# Converter.net
KiCad netlist of a schematic drawn in Altium Designer
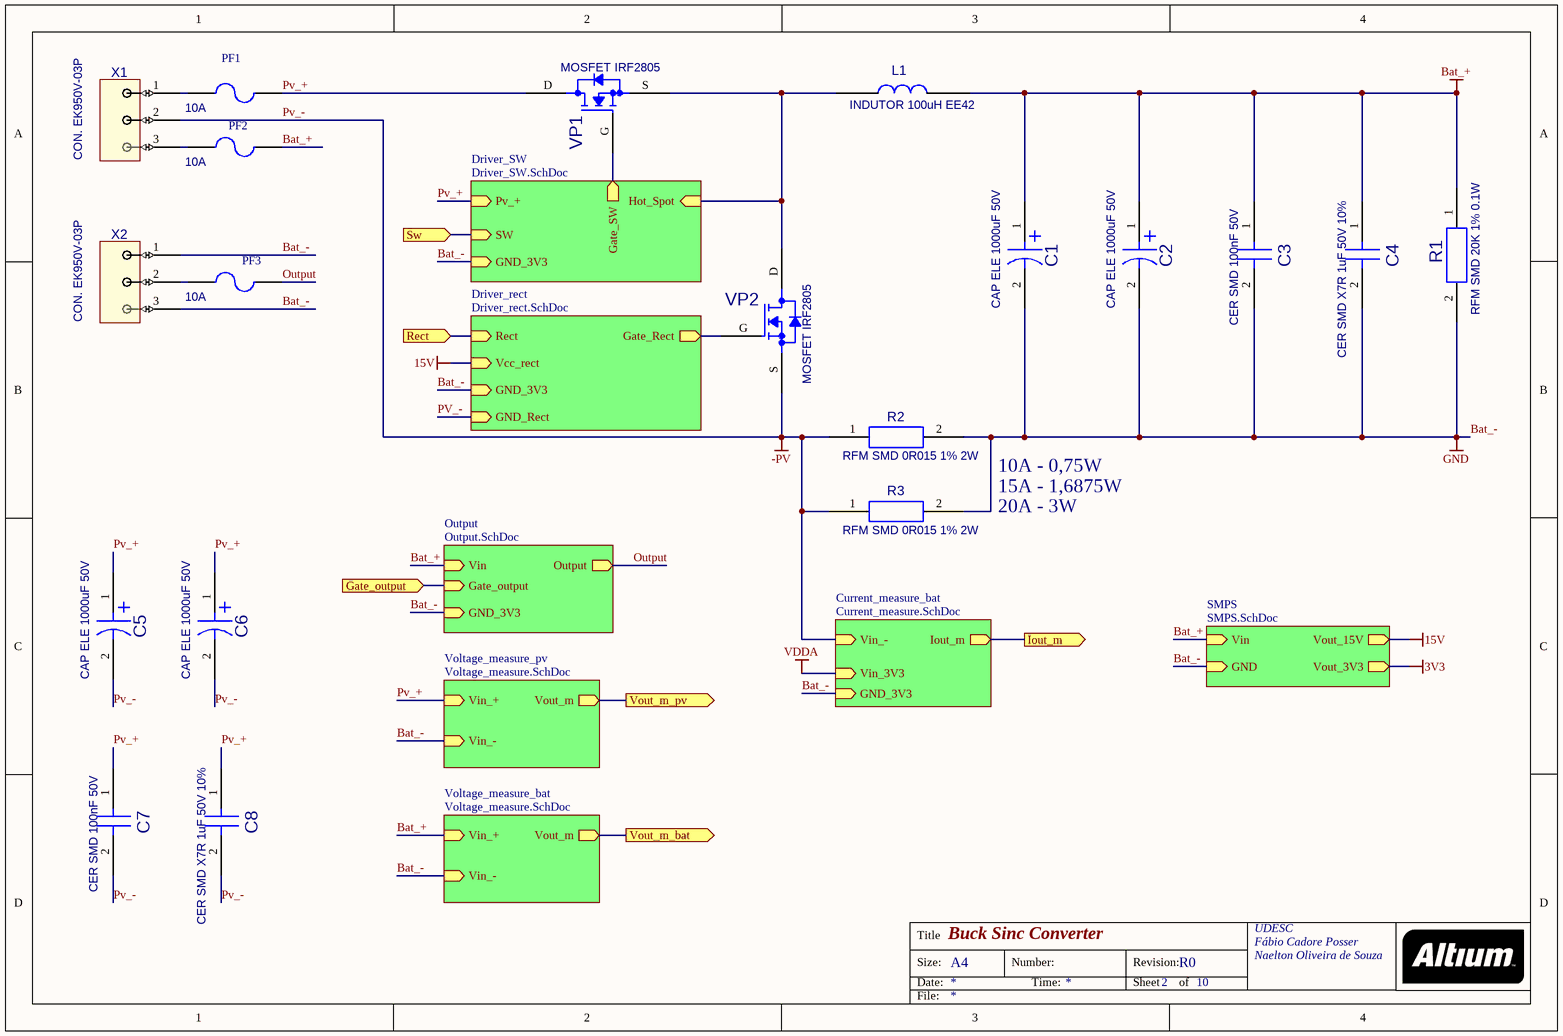
[diagram p0: Converter.SchDoc]

(export (version "E")
  (design (tool "Eeschema 10.0.6"))
  (components
    (comp (ref "C1")
      (value "CAP ELE 1000uF 50V")
      (footprint "CR 1.1 7.62 16.5")
      (fields (field (name "Comment") "10190340"))
      (libsource (lib "Buck_Converter") (part "10190340"))
    )
    (comp (ref "C2")
      (value "CAP ELE 1000uF 50V")
      (footprint "CR 1.1 7.62 16.5")
      (fields (field (name "Comment") "10190340"))
      (libsource (lib "Buck_Converter") (part "10190340"))
    )
    (comp (ref "C3")
      (value "CER SMD 100nF 50V")
      (footprint "C0805_R_V0")
      (fields (field (name "Comment") "10192075"))
      (libsource (lib "Buck_Converter") (part "10192075"))
    )
    (comp (ref "C4")
      (value "CER SMD X7R 1uF 50V 10%")
      (footprint "C0805_R_V0")
      (fields (field (name "Comment") "11736520"))
      (libsource (lib "Buck_Converter") (part "11736520"))
    )
    (comp (ref "C5")
      (value "CAP ELE 1000uF 50V")
      (footprint "CR 1.1 7.62 16.5")
      (fields (field (name "Comment") "10190340"))
      (libsource (lib "Buck_Converter") (part "10190340"))
    )
    (comp (ref "C6")
      (value "CAP ELE 1000uF 50V")
      (footprint "CR 1.1 7.62 16.5")
      (fields (field (name "Comment") "10190340"))
      (libsource (lib "Buck_Converter") (part "10190340"))
    )
    (comp (ref "C7")
      (value "CER SMD 100nF 50V")
      (footprint "C0805_R_V0")
      (fields (field (name "Comment") "10192075"))
      (libsource (lib "Buck_Converter") (part "10192075"))
    )
    (comp (ref "C8")
      (value "CER SMD X7R 1uF 50V 10%")
      (footprint "C0805_R_V0")
      (fields (field (name "Comment") "11736520"))
      (libsource (lib "Buck_Converter") (part "11736520"))
    )
    (comp (ref "L1")
      (value "INDUTOR 100uH EE42")
      (footprint "INDUTOR EE42_V1")
      (description "INDUTOR 560uH 4A PCV-2")
      (libsource (lib "Buck_Converter") (part "12578205"))
    )
    (comp (ref "PF1")
      (value "10A")
      (footprint "Fuse_holder")
      (fields (field (name "PUBLISHER") "Altium Limited"))
      (libsource (lib "Generic_altium lib_R0") (part "Fuse 2"))
    )
    (comp (ref "PF2")
      (value "10A")
      (footprint "Fuse_holder")
      (description "Fuse")
      (fields (field (name "PUBLISHER") "Altium Limited"))
      (libsource (lib "Generic_altium lib_R0") (part "Fuse 2"))
    )
    (comp (ref "PF3")
      (value "10A")
      (footprint "Fuse_holder")
      (description "Fuse")
      (fields (field (name "PUBLISHER") "Altium Limited"))
      (libsource (lib "Generic_altium lib_R0") (part "Fuse 2"))
    )
    (comp (ref "R1")
      (value "RFM SMD 20K 1% 0.1W")
      (footprint "R0805A")
      (fields (field (name "Comment") "10191996"))
      (libsource (lib "WEG LIB") (part "10191996"))
    )
    (comp (ref "R2")
      (value "RFM SMD 0R015 1% 2W")
      (footprint "WSL2816A")
      (fields (field (name "Comment") "11372881"))
      (libsource (lib "Buck_Converter") (part "11372881"))
    )
    (comp (ref "R3")
      (value "RFM SMD 0R015 1% 2W")
      (footprint "WSL2816A")
      (fields (field (name "Comment") "11372881"))
      (libsource (lib "Buck_Converter") (part "11372881"))
    )
    (comp (ref "VP1")
      (value "MOSFET IRF2805")
      (footprint "TO-220AB_V1")
      (description "MOSFET IRFB31N20D")
      (fields (field (name "Comment") "10190449"))
      (libsource (lib "Buck_Converter") (part "10190449"))
    )
    (comp (ref "VP2")
      (value "MOSFET IRF2805")
      (footprint "TO-220AB_V1")
      (description "MOSFET IRFB31N20D")
      (fields (field (name "Comment") "10190449"))
      (libsource (lib "Buck_Converter") (part "10190449"))
    )
    (comp (ref "X1")
      (value "CON. EK950V-03P")
      (footprint "662-A-111/03-SM")
      (fields (field (name "Comment") "10233722"))
      (libsource (lib "Buck_Converter") (part "10233722"))
    )
    (comp (ref "X2")
      (value "CON. EK950V-03P")
      (footprint "662-A-111/03-SM")
      (fields (field (name "Comment") "10233722"))
      (libsource (lib "Buck_Converter") (part "10233722"))
    )
  )
  (nets
    (net (code "1") (name "-PV") (class "Default")
      (node (ref "C5") (pin "2") (pinfunction "2_2") (pintype "passive"))
      (node (ref "C6") (pin "2") (pinfunction "2_2") (pintype "passive"))
      (node (ref "C7") (pin "2") (pinfunction "2_2") (pintype "passive"))
      (node (ref "C8") (pin "2") (pinfunction "2_2") (pintype "passive"))
      (node (ref "R2") (pin "1") (pinfunction "1_1") (pintype "passive"))
      (node (ref "R3") (pin "1") (pinfunction "1_1") (pintype "passive"))
      (node (ref "VP2") (pin "S") (pinfunction "3_S") (pintype "passive"))
      (node (ref "X1") (pin "2") (pinfunction "2_2") (pintype "bidirectional"))
    )
    (net (code "2") (name "/Gate_Rect") (class "Default")
      (node (ref "VP2") (pin "G") (pinfunction "1_G") (pintype "passive"))
    )
    (net (code "3") (name "/Gate_SW") (class "Default")
      (node (ref "VP1") (pin "G") (pinfunction "1_G") (pintype "passive"))
    )
    (net (code "5") (name "/Hot_Spot") (class "Default")
      (node (ref "L1") (pin "1") (pinfunction "1_1") (pintype "passive"))
      (node (ref "VP1") (pin "S") (pinfunction "3_S") (pintype "passive"))
      (node (ref "VP2") (pin "D") (pinfunction "2_D") (pintype "passive"))
    )
    (net (code "7") (name "/Output") (class "Default")
      (node (ref "PF3") (pin "2") (pinfunction "2_2") (pintype "passive"))
    )
    (net (code "9") (name "/Pv_+") (class "Default")
      (node (ref "C5") (pin "1") (pinfunction "1_1") (pintype "passive"))
      (node (ref "C6") (pin "1") (pinfunction "1_1") (pintype "passive"))
      (node (ref "C7") (pin "1") (pinfunction "1_1") (pintype "passive"))
      (node (ref "C8") (pin "1") (pinfunction "1_1") (pintype "passive"))
      (node (ref "PF1") (pin "2") (pinfunction "2_2") (pintype "passive"))
      (node (ref "VP1") (pin "D") (pinfunction "2_D") (pintype "passive"))
    )
    (net (code "16") (name "Bat_+") (class "Default")
      (node (ref "C1") (pin "1") (pinfunction "1_1") (pintype "passive"))
      (node (ref "C2") (pin "1") (pinfunction "1_1") (pintype "passive"))
      (node (ref "C3") (pin "1") (pinfunction "1_1") (pintype "passive"))
      (node (ref "C4") (pin "1") (pinfunction "1_1") (pintype "passive"))
      (node (ref "L1") (pin "2") (pinfunction "2_2") (pintype "passive"))
      (node (ref "PF2") (pin "2") (pinfunction "2_2") (pintype "passive"))
      (node (ref "R1") (pin "1") (pinfunction "1_1") (pintype "passive"))
    )
    (net (code "17") (name "GND") (class "Default")
      (node (ref "C1") (pin "2") (pinfunction "2_2") (pintype "passive"))
      (node (ref "C2") (pin "2") (pinfunction "2_2") (pintype "passive"))
      (node (ref "C3") (pin "2") (pinfunction "2_2") (pintype "passive"))
      (node (ref "C4") (pin "2") (pinfunction "2_2") (pintype "passive"))
      (node (ref "R1") (pin "2") (pinfunction "2_2") (pintype "passive"))
      (node (ref "R2") (pin "2") (pinfunction "2_2") (pintype "passive"))
      (node (ref "R3") (pin "2") (pinfunction "2_2") (pintype "passive"))
      (node (ref "X2") (pin "1") (pinfunction "1_1") (pintype "bidirectional"))
      (node (ref "X2") (pin "3") (pinfunction "3_3") (pintype "bidirectional"))
    )
    (net (code "18") (name "Net-(PF1-Pad1)") (class "Default")
      (node (ref "PF1") (pin "1") (pinfunction "1_1") (pintype "passive"))
      (node (ref "X1") (pin "1") (pinfunction "1_1") (pintype "bidirectional"))
    )
    (net (code "19") (name "Net-(PF2-Pad1)") (class "Default")
      (node (ref "PF2") (pin "1") (pinfunction "1_1") (pintype "passive"))
      (node (ref "X1") (pin "3") (pinfunction "3_3") (pintype "bidirectional"))
    )
    (net (code "20") (name "Net-(PF3-Pad1)") (class "Default")
      (node (ref "PF3") (pin "1") (pinfunction "1_1") (pintype "passive"))
      (node (ref "X2") (pin "2") (pinfunction "2_2") (pintype "bidirectional"))
    )
  )
)
